# power.net
KiCad netlist of a schematic drawn in Altium Designer
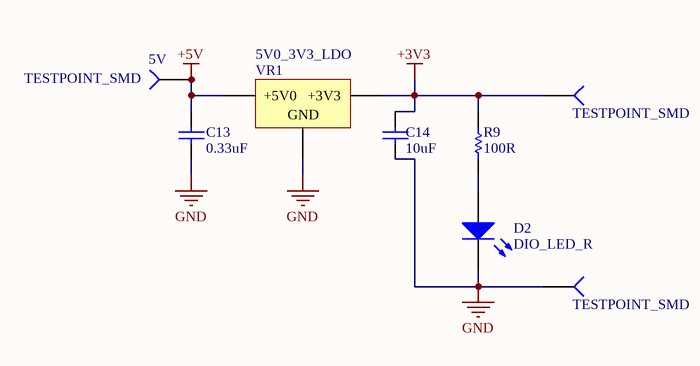
[diagram p0: power.SchDoc]

(export (version "E")
  (design (tool "Eeschema 10.0.6"))
  (components
    (comp (ref "3V3")
      (value "TESTPOINT_SMD")
      (footprint "TESTPOINT")
      (libsource (lib "UWRT_Schematic_Library_2019") (part "TESTPOINT_SMD"))
    )
    (comp (ref "5V")
      (value "TESTPOINT_SMD")
      (footprint "TESTPOINT")
      (libsource (lib "UWRT_Schematic_Library_2019") (part "TESTPOINT_SMD"))
    )
    (comp (ref "C13")
      (value "0.33uF")
      (footprint "CAPC0603(1608)55_N")
      (description "CAP CER 0.33UF 16V X7R 0603")
      (fields
        (field (name "MANUFACTURER") "Murata Electronics North America")
        (field (name "MPN") "GCM188R71C334KA37D")
      )
      (libsource (lib "UWRT_Schematic_Library_2019") (part "CAP_0.33uF_16V_0603"))
    )
    (comp (ref "C14")
      (value "10uF")
      (footprint "AVX-CAPC3528_V")
      (description "CAP CER 10UF 10V X5R 0603")
      (fields (field (name "MANUFACTURER") "Yageo") (field (name "MPN") "CC0603MRX5R6BB106"))
      (libsource (lib "UWRT_Schematic_Library_2019") (part "CAP_10uF_0603"))
    )
    (comp (ref "D2")
      (value "DIO_LED_R")
      (footprint "LED_0805_LINE")
      (description "LED RED DIFFUSED 0805 SMD")
      (fields (field (name "MANUFACTURER") "OSRAM") (field (name "MPN") "LS R976-NR-1"))
      (libsource (lib "UWRT_Schematic_Library_2019") (part "DIO_LED_R"))
    )
    (comp (ref "GND")
      (value "TESTPOINT_SMD")
      (footprint "TESTPOINT")
      (libsource (lib "UWRT_Schematic_Library_2019") (part "TESTPOINT_SMD"))
    )
    (comp (ref "R9")
      (value "100R")
      (footprint "RESC0603(1608)_N")
      (description "RES SMD 100 OHM 1% 1/10W 0603")
      (fields (field (name "MANUFACTURER") "Yageo") (field (name "TOLERANCE") "1%"))
      (libsource (lib "UWRT_Schematic_Library_2019") (part "RES_100R_0603"))
    )
    (comp (ref "VR1")
      (value "5V0_3V3_LDO")
      (footprint "UWRT_Footprint_Library_2019:VOLTAGE_REGULATOR")
      (description "IC REG LINEAR 3.3V 1A DPAK")
      (fields (field (name "MANUFACTURER") "ON Semiconductor") (field (name "MPN") "NCP1117DT33T5G"))
      (libsource (lib "UWRT_Schematic_Library_2019") (part "5V0_3V3_LDO"))
    )
  )
  (nets
    (net (code "1") (name "+3V3") (class "Default")
      (node (ref "3V3") (pin "1") (pinfunction "=value_1") (pintype "passive"))
      (node (ref "C14") (pin "2") (pinfunction "2_2") (pintype "passive"))
      (node (ref "R9") (pin "2") (pinfunction "2_2") (pintype "passive"))
      (node (ref "VR1") (pin "2") (pinfunction "+3V3_2") (pintype "passive"))
    )
    (net (code "2") (name "+5V") (class "Default")
      (node (ref "5V") (pin "1") (pinfunction "=value_1") (pintype "passive"))
      (node (ref "C13") (pin "2") (pinfunction "2_2") (pintype "passive"))
      (node (ref "VR1") (pin "3") (pinfunction "+5V0_3") (pintype "passive"))
    )
    (net (code "3") (name "GND") (class "Default")
      (node (ref "C13") (pin "1") (pinfunction "1_1") (pintype "passive"))
      (node (ref "C14") (pin "1") (pinfunction "1_1") (pintype "passive"))
      (node (ref "D2") (pin "2") (pinfunction "K_2") (pintype "passive"))
      (node (ref "GND") (pin "1") (pinfunction "=value_1") (pintype "passive"))
      (node (ref "VR1") (pin "1") (pinfunction "GND_1") (pintype "passive"))
    )
    (net (code "4") (name "Net-(D2-A)") (class "Default")
      (node (ref "D2") (pin "1") (pinfunction "A_1") (pintype "passive"))
      (node (ref "R9") (pin "1") (pinfunction "1_1") (pintype "passive"))
    )
  )
)
